# rom-programmer.net
KiCad netlist of a schematic drawn in EAGLE
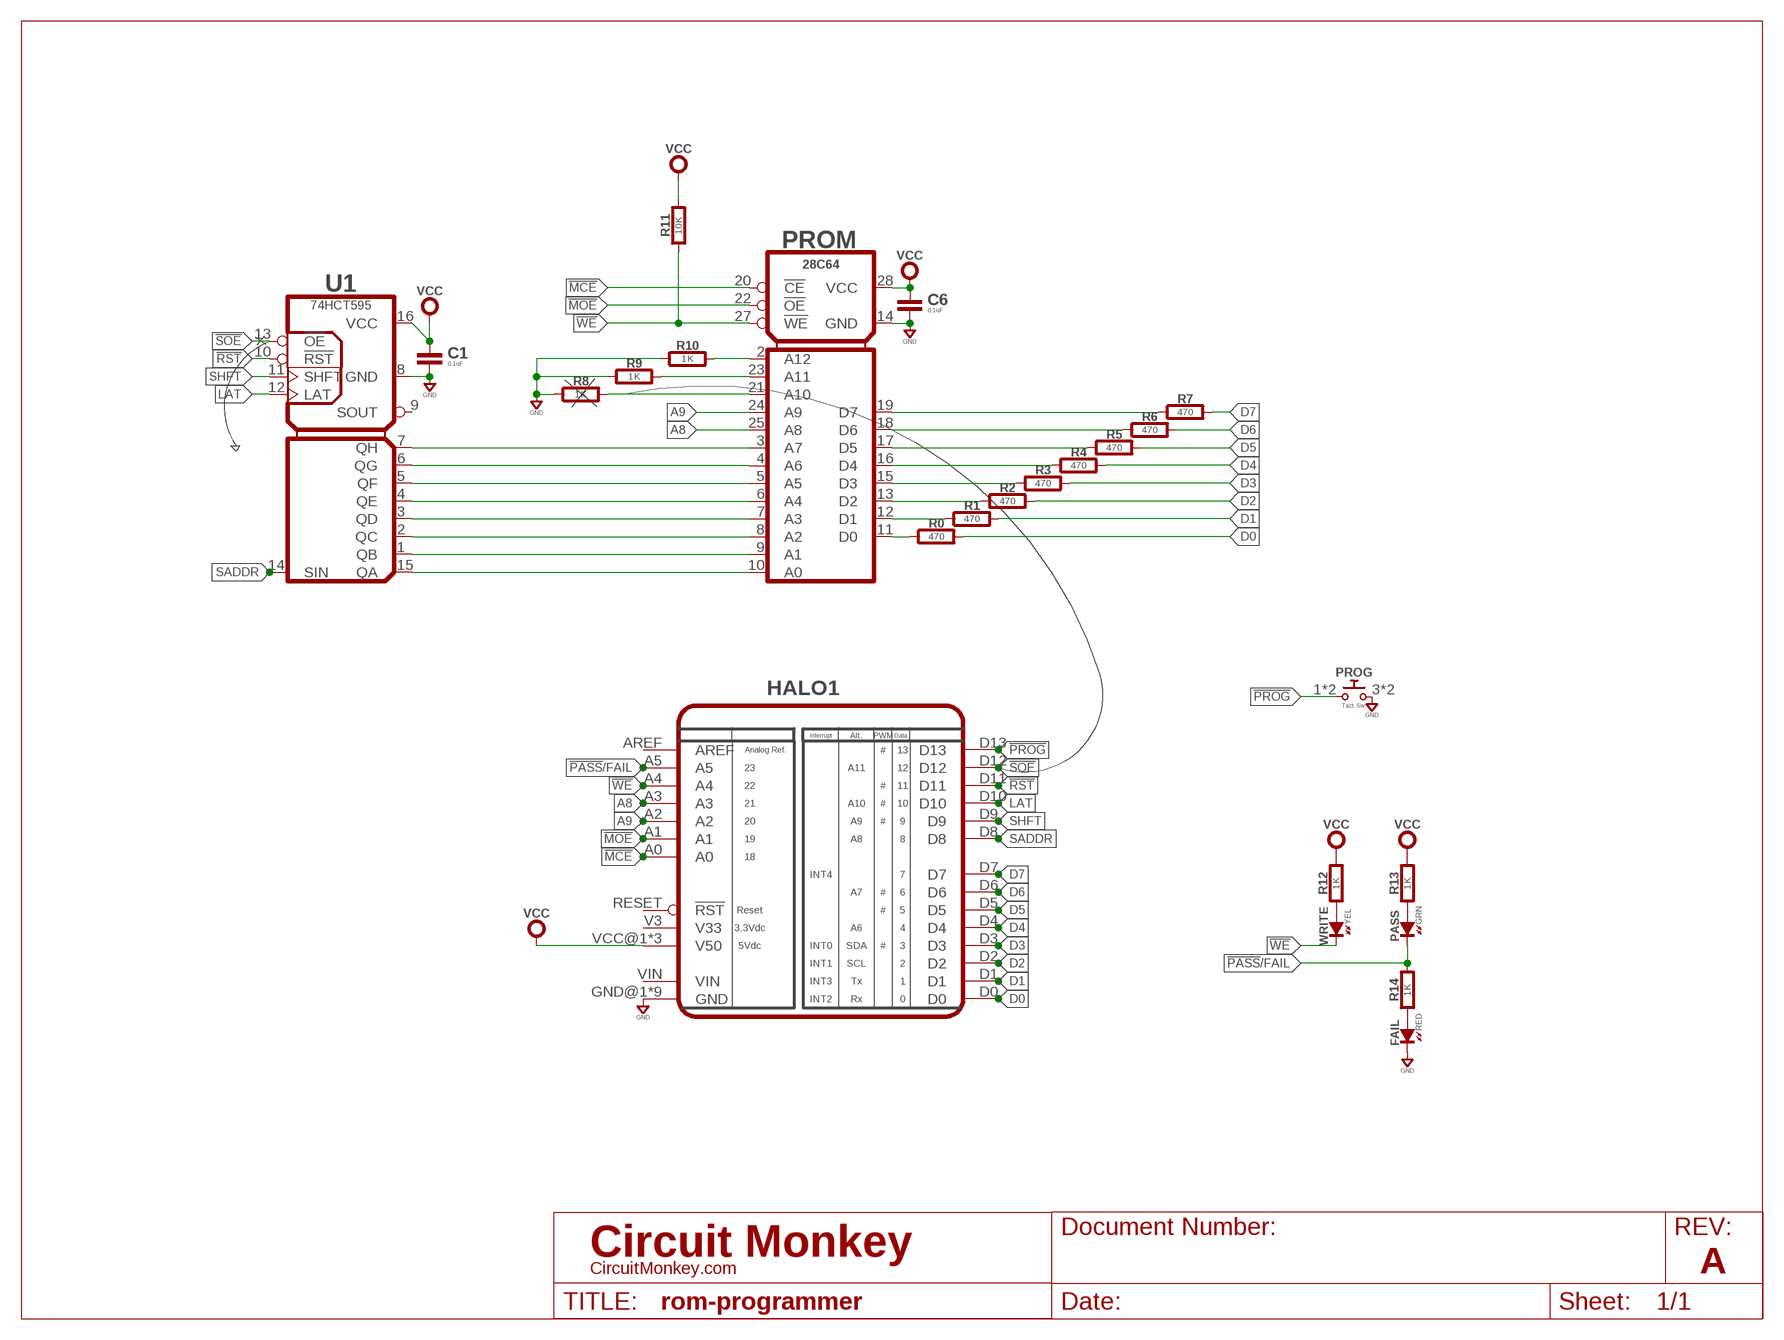
[diagram p0: schematic, sheet 1]

(export (version "E")
  (design (tool "Eeschema 10.0.6"))
  (components
    (comp (ref "C1")
      (value "0.1uF")
      (footprint "eagle-import:0603-CAP")
      (libsource (lib "eagle-import") (part "CAPACITOR0603"))
    )
    (comp (ref "C6")
      (value "0.1uF")
      (footprint "eagle-import:0603-CAP")
      (libsource (lib "eagle-import") (part "CAPACITOR0603"))
    )
    (comp (ref "FAIL")
      (value "RED")
      (footprint "eagle-import:SMD_0603")
      (libsource (lib "eagle-import") (part "SMT0603"))
    )
    (comp (ref "HALO1")
      (value "HALO-A2")
      (footprint "eagle-import:PCB-HALO-A2-PINS")
      (libsource (lib "eagle-import") (part "HALO-A2"))
    )
    (comp (ref "PASS")
      (value "GRN")
      (footprint "eagle-import:SMD_0603")
      (libsource (lib "eagle-import") (part "SMT0603"))
    )
    (comp (ref "PROG")
      (value "Tact. Sw.")
      (footprint "eagle-import:B3FS")
      (fields (field (name "MFR") "Omron") (field (name "MPN") "B3FS-10*"))
      (libsource (lib "eagle-import") (part "PUSHBTN-MOMB3FS"))
    )
    (comp (ref "PROM")
      (value "28C64")
      (footprint "eagle-import:SO28")
      (fields (field (name "MFR") "Microchip") (field (name "MPN") "AT28C64B-15SU"))
      (libsource (lib "eagle-import") (part "2864?SC"))
    )
    (comp (ref "R0")
      (value "470")
      (footprint "eagle-import:0603-RES")
      (libsource (lib "eagle-import") (part "RESISTOR0603"))
    )
    (comp (ref "R1")
      (value "470")
      (footprint "eagle-import:0603-RES")
      (libsource (lib "eagle-import") (part "RESISTOR0603"))
    )
    (comp (ref "R2")
      (value "470")
      (footprint "eagle-import:0603-RES")
      (libsource (lib "eagle-import") (part "RESISTOR0603"))
    )
    (comp (ref "R3")
      (value "470")
      (footprint "eagle-import:0603-RES")
      (libsource (lib "eagle-import") (part "RESISTOR0603"))
    )
    (comp (ref "R4")
      (value "470")
      (footprint "eagle-import:0603-RES")
      (libsource (lib "eagle-import") (part "RESISTOR0603"))
    )
    (comp (ref "R5")
      (value "470")
      (footprint "eagle-import:0603-RES")
      (libsource (lib "eagle-import") (part "RESISTOR0603"))
    )
    (comp (ref "R6")
      (value "470")
      (footprint "eagle-import:0603-RES")
      (libsource (lib "eagle-import") (part "RESISTOR0603"))
    )
    (comp (ref "R7")
      (value "470")
      (footprint "eagle-import:0603-RES")
      (libsource (lib "eagle-import") (part "RESISTOR0603"))
    )
    (comp (ref "R8")
      (value "1K")
      (footprint "eagle-import:0603-RES")
      (libsource (lib "eagle-import") (part "RESISTOR0603"))
    )
    (comp (ref "R9")
      (value "1K")
      (footprint "eagle-import:0603-RES")
      (libsource (lib "eagle-import") (part "RESISTOR0603"))
    )
    (comp (ref "R10")
      (value "1K")
      (footprint "eagle-import:0603-RES")
      (libsource (lib "eagle-import") (part "RESISTOR0603"))
    )
    (comp (ref "R11")
      (value "10K")
      (footprint "eagle-import:0603-RES")
      (libsource (lib "eagle-import") (part "RESISTOR0603"))
    )
    (comp (ref "R12")
      (value "1K")
      (footprint "eagle-import:0603-RES")
      (libsource (lib "eagle-import") (part "RESISTOR0603"))
    )
    (comp (ref "R13")
      (value "1K")
      (footprint "eagle-import:0603-RES")
      (libsource (lib "eagle-import") (part "RESISTOR0603"))
    )
    (comp (ref "R14")
      (value "1K")
      (footprint "eagle-import:0603-RES")
      (libsource (lib "eagle-import") (part "RESISTOR0603"))
    )
    (comp (ref "U1")
      (value "74HCT595")
      (footprint "eagle-import:SO16")
      (fields (field (name "MFR") "ON Semi") (field (name "MPN") "74HCT595ADG"))
      (libsource (lib "eagle-import") (part "74595AD?GHCT"))
    )
    (comp (ref "WRITE")
      (value "YEL")
      (footprint "eagle-import:SMD_0603")
      (libsource (lib "eagle-import") (part "SMT0603"))
    )
  )
  (nets
    (net (code "1") (name "/~{MCE}") (class "Default")
      (node (ref "HALO1") (pin "A0") (pinfunction "A0_A0") (pintype "bidirectional"))
      (node (ref "PROM") (pin "20") (pinfunction "~{CE}_20") (pintype "input"))
    )
    (net (code "2") (name "/~{MOE}") (class "Default")
      (node (ref "HALO1") (pin "A1") (pinfunction "A1_A1") (pintype "bidirectional"))
      (node (ref "PROM") (pin "22") (pinfunction "~{OE}_22") (pintype "input"))
    )
    (net (code "3") (name "/~{PASS}{slash}FAIL") (class "Default")
      (node (ref "HALO1") (pin "A5") (pinfunction "A5_A5") (pintype "bidirectional"))
      (node (ref "PASS") (pin "K") (pinfunction "C_K") (pintype "passive"))
      (node (ref "R14") (pin "2") (pinfunction "2_2") (pintype "passive"))
    )
    (net (code "4") (name "/~{PROG}") (class "Default")
      (node (ref "HALO1") (pin "D13") (pinfunction "D13_D13") (pintype "bidirectional"))
      (node (ref "PROG") (pin "1") (pinfunction "1_1") (pintype "passive"))
      (node (ref "PROG") (pin "2") (pinfunction "1_2") (pintype "passive"))
    )
    (net (code "5") (name "/~{RST}") (class "Default")
      (node (ref "HALO1") (pin "D11") (pinfunction "D11_D11") (pintype "bidirectional"))
      (node (ref "U1") (pin "10") (pinfunction "~{RST}_10") (pintype "bidirectional"))
    )
    (net (code "6") (name "/~{SOE}") (class "Default")
      (node (ref "HALO1") (pin "D12") (pinfunction "D12_D12") (pintype "bidirectional"))
      (node (ref "U1") (pin "13") (pinfunction "~{OE}_13") (pintype "bidirectional"))
    )
    (net (code "7") (name "/~{WE}") (class "Default")
      (node (ref "HALO1") (pin "A4") (pinfunction "A4_A4") (pintype "bidirectional"))
      (node (ref "PROM") (pin "27") (pinfunction "~{WE}_27") (pintype "input"))
      (node (ref "R11") (pin "1") (pinfunction "1_1") (pintype "passive"))
      (node (ref "WRITE") (pin "K") (pinfunction "C_K") (pintype "passive"))
    )
    (net (code "8") (name "A8") (class "Default")
      (node (ref "HALO1") (pin "A3") (pinfunction "A3_A3") (pintype "bidirectional"))
      (node (ref "PROM") (pin "25") (pinfunction "A8_25") (pintype "input"))
    )
    (net (code "9") (name "A9") (class "Default")
      (node (ref "HALO1") (pin "A2") (pinfunction "A2_A2") (pintype "bidirectional"))
      (node (ref "PROM") (pin "24") (pinfunction "A9_24") (pintype "input"))
    )
    (net (code "10") (name "D0") (class "Default")
      (node (ref "HALO1") (pin "D0") (pinfunction "D0_D0") (pintype "bidirectional"))
      (node (ref "R0") (pin "2") (pinfunction "2_2") (pintype "passive"))
    )
    (net (code "11") (name "D1") (class "Default")
      (node (ref "HALO1") (pin "D1") (pinfunction "D1_D1") (pintype "bidirectional"))
      (node (ref "R1") (pin "2") (pinfunction "2_2") (pintype "passive"))
    )
    (net (code "12") (name "D2") (class "Default")
      (node (ref "HALO1") (pin "D2") (pinfunction "D2_D2") (pintype "bidirectional"))
      (node (ref "R2") (pin "2") (pinfunction "2_2") (pintype "passive"))
    )
    (net (code "13") (name "D3") (class "Default")
      (node (ref "HALO1") (pin "D3") (pinfunction "D3_D3") (pintype "bidirectional"))
      (node (ref "R3") (pin "2") (pinfunction "2_2") (pintype "passive"))
    )
    (net (code "14") (name "D4") (class "Default")
      (node (ref "HALO1") (pin "D4") (pinfunction "D4_D4") (pintype "bidirectional"))
      (node (ref "R4") (pin "2") (pinfunction "2_2") (pintype "passive"))
    )
    (net (code "15") (name "D5") (class "Default")
      (node (ref "HALO1") (pin "D5") (pinfunction "D5_D5") (pintype "bidirectional"))
      (node (ref "R5") (pin "2") (pinfunction "2_2") (pintype "passive"))
    )
    (net (code "16") (name "D6") (class "Default")
      (node (ref "HALO1") (pin "D6") (pinfunction "D6_D6") (pintype "bidirectional"))
      (node (ref "R6") (pin "2") (pinfunction "2_2") (pintype "passive"))
    )
    (net (code "17") (name "D7") (class "Default")
      (node (ref "HALO1") (pin "D7") (pinfunction "D7_D7") (pintype "bidirectional"))
      (node (ref "R7") (pin "2") (pinfunction "2_2") (pintype "passive"))
    )
    (net (code "18") (name "GND") (class "Default")
      (node (ref "C1") (pin "2") (pinfunction "2_2") (pintype "passive"))
      (node (ref "C6") (pin "2") (pinfunction "2_2") (pintype "passive"))
      (node (ref "FAIL") (pin "K") (pinfunction "C_K") (pintype "passive"))
      (node (ref "HALO1") (pin "GND@1") (pinfunction "GND_GND@1") (pintype "bidirectional"))
      (node (ref "HALO1") (pin "GND@1.2") (pinfunction "GND_GND@1.2") (pintype "bidirectional"))
      (node (ref "HALO1") (pin "GND@2") (pinfunction "GND_GND@2") (pintype "bidirectional"))
      (node (ref "HALO1") (pin "GND@3") (pinfunction "GND_GND@3") (pintype "bidirectional"))
      (node (ref "HALO1") (pin "GND@4") (pinfunction "GND_GND@4") (pintype "bidirectional"))
      (node (ref "HALO1") (pin "MTG1") (pinfunction "GND_MTG1") (pintype "bidirectional"))
      (node (ref "HALO1") (pin "MTG2") (pinfunction "GND_MTG2") (pintype "bidirectional"))
      (node (ref "HALO1") (pin "MTG3") (pinfunction "GND_MTG3") (pintype "bidirectional"))
      (node (ref "HALO1") (pin "MTG4") (pinfunction "GND_MTG4") (pintype "bidirectional"))
      (node (ref "PROG") (pin "3") (pinfunction "2_3") (pintype "passive"))
      (node (ref "PROG") (pin "4") (pinfunction "2_4") (pintype "passive"))
      (node (ref "PROM") (pin "14") (pinfunction "GND_14") (pintype "power_in"))
      (node (ref "R10") (pin "1") (pinfunction "1_1") (pintype "passive"))
      (node (ref "R8") (pin "1") (pinfunction "1_1") (pintype "passive"))
      (node (ref "R9") (pin "1") (pinfunction "1_1") (pintype "passive"))
      (node (ref "U1") (pin "8") (pinfunction "GND_8") (pintype "bidirectional"))
    )
    (net (code "19") (name "LAT") (class "Default")
      (node (ref "HALO1") (pin "D10") (pinfunction "D10_D10") (pintype "bidirectional"))
      (node (ref "U1") (pin "12") (pinfunction "LAT_12") (pintype "bidirectional"))
    )
    (net (code "20") (name "Net-(FAIL-PadA)") (class "Default")
      (node (ref "FAIL") (pin "A") (pinfunction "A_A") (pintype "passive"))
      (node (ref "R14") (pin "1") (pinfunction "1_1") (pintype "passive"))
    )
    (net (code "21") (name "Net-(PASS-PadA)") (class "Default")
      (node (ref "PASS") (pin "A") (pinfunction "A_A") (pintype "passive"))
      (node (ref "R13") (pin "1") (pinfunction "1_1") (pintype "passive"))
    )
    (net (code "22") (name "Net-(PROM-A0)") (class "Default")
      (node (ref "PROM") (pin "10") (pinfunction "A0_10") (pintype "input"))
      (node (ref "U1") (pin "15") (pinfunction "QA_15") (pintype "bidirectional"))
    )
    (net (code "23") (name "Net-(PROM-A1)") (class "Default")
      (node (ref "PROM") (pin "9") (pinfunction "A1_9") (pintype "input"))
      (node (ref "U1") (pin "1") (pinfunction "QB_1") (pintype "bidirectional"))
    )
    (net (code "24") (name "Net-(PROM-A2)") (class "Default")
      (node (ref "PROM") (pin "8") (pinfunction "A2_8") (pintype "input"))
      (node (ref "U1") (pin "2") (pinfunction "QC_2") (pintype "bidirectional"))
    )
    (net (code "25") (name "Net-(PROM-A3)") (class "Default")
      (node (ref "PROM") (pin "7") (pinfunction "A3_7") (pintype "input"))
      (node (ref "U1") (pin "3") (pinfunction "QD_3") (pintype "bidirectional"))
    )
    (net (code "26") (name "Net-(PROM-A4)") (class "Default")
      (node (ref "PROM") (pin "6") (pinfunction "A4_6") (pintype "input"))
      (node (ref "U1") (pin "4") (pinfunction "QE_4") (pintype "bidirectional"))
    )
    (net (code "27") (name "Net-(PROM-A5)") (class "Default")
      (node (ref "PROM") (pin "5") (pinfunction "A5_5") (pintype "input"))
      (node (ref "U1") (pin "5") (pinfunction "QF_5") (pintype "bidirectional"))
    )
    (net (code "28") (name "Net-(PROM-A6)") (class "Default")
      (node (ref "PROM") (pin "4") (pinfunction "A6_4") (pintype "input"))
      (node (ref "U1") (pin "6") (pinfunction "QG_6") (pintype "bidirectional"))
    )
    (net (code "29") (name "Net-(PROM-A7)") (class "Default")
      (node (ref "PROM") (pin "3") (pinfunction "A7_3") (pintype "input"))
      (node (ref "U1") (pin "7") (pinfunction "QH_7") (pintype "bidirectional"))
    )
    (net (code "30") (name "Net-(PROM-A10)") (class "Default")
      (node (ref "PROM") (pin "21") (pinfunction "A10_21") (pintype "input"))
      (node (ref "R8") (pin "2") (pinfunction "2_2") (pintype "passive"))
    )
    (net (code "31") (name "Net-(PROM-A11)") (class "Default")
      (node (ref "PROM") (pin "23") (pinfunction "A11_23") (pintype "input"))
      (node (ref "R9") (pin "2") (pinfunction "2_2") (pintype "passive"))
    )
    (net (code "32") (name "Net-(PROM-A12)") (class "Default")
      (node (ref "PROM") (pin "2") (pinfunction "A12_2") (pintype "input"))
      (node (ref "R10") (pin "2") (pinfunction "2_2") (pintype "passive"))
    )
    (net (code "33") (name "Net-(PROM-D0)") (class "Default")
      (node (ref "PROM") (pin "11") (pinfunction "D0_11") (pintype "bidirectional"))
      (node (ref "R0") (pin "1") (pinfunction "1_1") (pintype "passive"))
    )
    (net (code "34") (name "Net-(PROM-D1)") (class "Default")
      (node (ref "PROM") (pin "12") (pinfunction "D1_12") (pintype "bidirectional"))
      (node (ref "R1") (pin "1") (pinfunction "1_1") (pintype "passive"))
    )
    (net (code "35") (name "Net-(PROM-D2)") (class "Default")
      (node (ref "PROM") (pin "13") (pinfunction "D2_13") (pintype "bidirectional"))
      (node (ref "R2") (pin "1") (pinfunction "1_1") (pintype "passive"))
    )
    (net (code "36") (name "Net-(PROM-D3)") (class "Default")
      (node (ref "PROM") (pin "15") (pinfunction "D3_15") (pintype "bidirectional"))
      (node (ref "R3") (pin "1") (pinfunction "1_1") (pintype "passive"))
    )
    (net (code "37") (name "Net-(PROM-D4)") (class "Default")
      (node (ref "PROM") (pin "16") (pinfunction "D4_16") (pintype "bidirectional"))
      (node (ref "R4") (pin "1") (pinfunction "1_1") (pintype "passive"))
    )
    (net (code "38") (name "Net-(PROM-D5)") (class "Default")
      (node (ref "PROM") (pin "17") (pinfunction "D5_17") (pintype "bidirectional"))
      (node (ref "R5") (pin "1") (pinfunction "1_1") (pintype "passive"))
    )
    (net (code "39") (name "Net-(PROM-D6)") (class "Default")
      (node (ref "PROM") (pin "18") (pinfunction "D6_18") (pintype "bidirectional"))
      (node (ref "R6") (pin "1") (pinfunction "1_1") (pintype "passive"))
    )
    (net (code "40") (name "Net-(PROM-D7)") (class "Default")
      (node (ref "PROM") (pin "19") (pinfunction "D7_19") (pintype "bidirectional"))
      (node (ref "R7") (pin "1") (pinfunction "1_1") (pintype "passive"))
    )
    (net (code "41") (name "Net-(R12-Pad1)") (class "Default")
      (node (ref "R12") (pin "1") (pinfunction "1_1") (pintype "passive"))
      (node (ref "WRITE") (pin "A") (pinfunction "A_A") (pintype "passive"))
    )
    (net (code "42") (name "SADDR") (class "Default")
      (node (ref "HALO1") (pin "D8") (pinfunction "D8_D8") (pintype "bidirectional"))
      (node (ref "U1") (pin "14") (pinfunction "SIN_14") (pintype "bidirectional"))
    )
    (net (code "43") (name "SHFT") (class "Default")
      (node (ref "HALO1") (pin "D9") (pinfunction "D9_D9") (pintype "bidirectional"))
      (node (ref "U1") (pin "11") (pinfunction "SHFT_11") (pintype "bidirectional"))
    )
    (net (code "44") (name "VCC") (class "Default")
      (node (ref "C1") (pin "1") (pinfunction "1_1") (pintype "passive"))
      (node (ref "C6") (pin "1") (pinfunction "1_1") (pintype "passive"))
      (node (ref "HALO1") (pin "VCC@1") (pinfunction "V50_VCC@1") (pintype "bidirectional"))
      (node (ref "HALO1") (pin "VCC@2") (pinfunction "V50_VCC@2") (pintype "bidirectional"))
      (node (ref "HALO1") (pin "VCC@3") (pinfunction "V50_VCC@3") (pintype "bidirectional"))
      (node (ref "PROM") (pin "28") (pinfunction "VCC_28") (pintype "power_in"))
      (node (ref "R11") (pin "2") (pinfunction "2_2") (pintype "passive"))
      (node (ref "R12") (pin "2") (pinfunction "2_2") (pintype "passive"))
      (node (ref "R13") (pin "2") (pinfunction "2_2") (pintype "passive"))
      (node (ref "U1") (pin "16") (pinfunction "VCC_16") (pintype "bidirectional"))
    )
    (net (code "45") (name "unconnected-(HALO1-PadAREF)") (class "Default")
      (node (ref "HALO1") (pin "AREF") (pinfunction "AREF_AREF") (pintype "bidirectional"))
    )
    (net (code "46") (name "unconnected-(HALO1-PadVIN)") (class "Default")
      (node (ref "HALO1") (pin "VIN") (pinfunction "VIN_VIN") (pintype "bidirectional"))
    )
    (net (code "47") (name "unconnected-(HALO1-V33-PadV3)") (class "Default")
      (node (ref "HALO1") (pin "V3") (pinfunction "V33_V3") (pintype "bidirectional"))
    )
    (net (code "48") (name "unconnected-(HALO1-~{RST}-PadRESET)") (class "Default")
      (node (ref "HALO1") (pin "RESET") (pinfunction "~{RST}_RESET") (pintype "bidirectional"))
    )
    (net (code "49") (name "unconnected-(U1-SOUT-Pad9)") (class "Default")
      (node (ref "U1") (pin "9") (pinfunction "SOUT_9") (pintype "bidirectional"))
    )
  )
)
